# 10_USB_HOST.net
KiCad netlist of a schematic drawn in Altium Designer
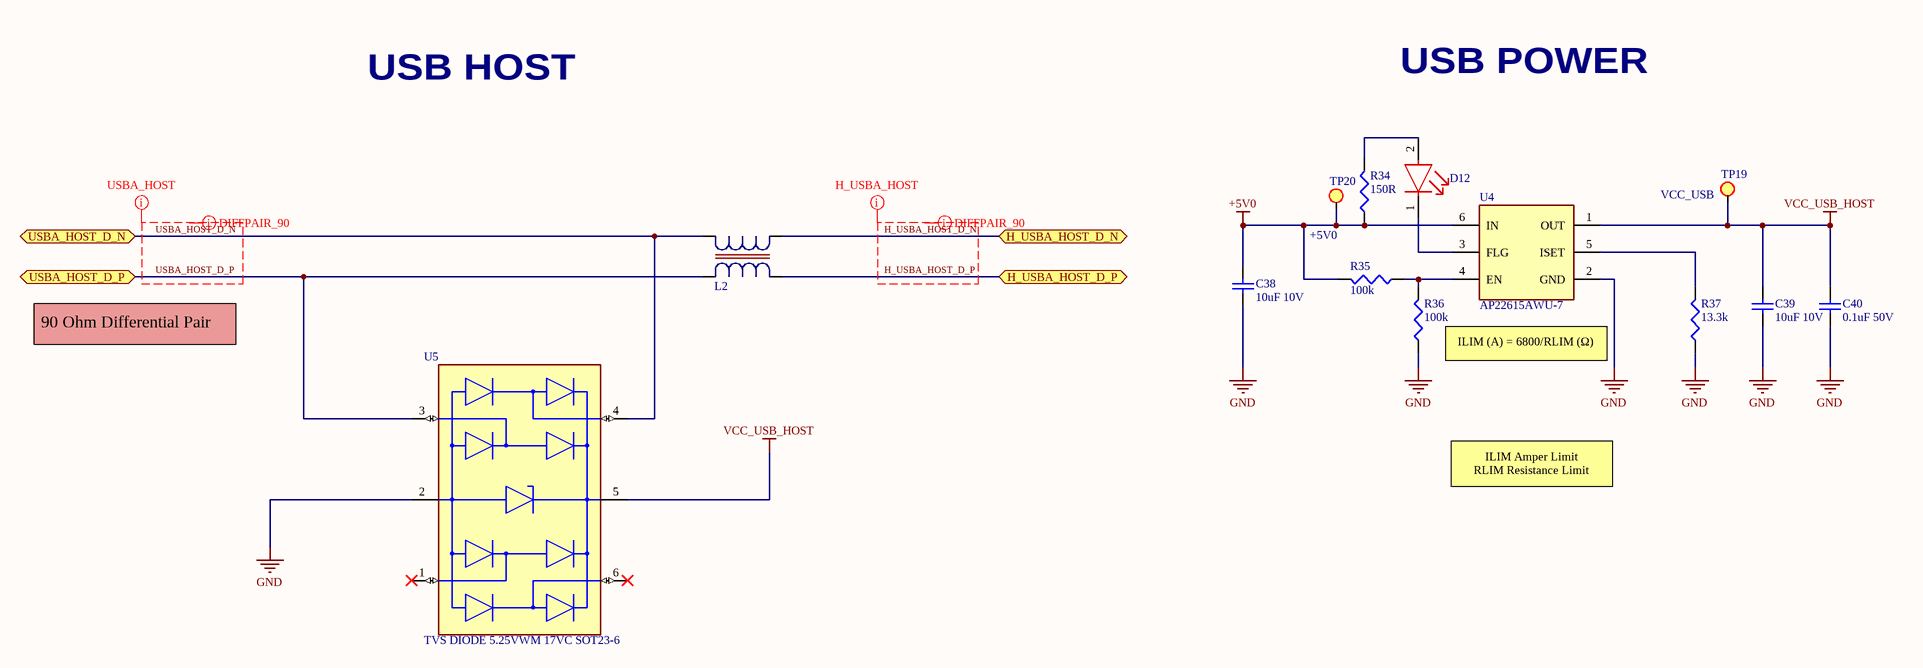
[diagram p0: 10_USB_HOST.SchDoc]

(export (version "E")
  (design (tool "Eeschema 10.0.6"))
  (components
    (comp (ref "C38")
      (value "10uF 10V")
      (footprint "SMC0603")
      (description "10 µF ±10% 10V Ceramic Capacitor X5R 0603 (1608 Metric)")
      (fields
        (field (name "MANUFACTURER PART NUMBER") "CL10A106KP8NNNC")
        (field (name "LCSC PART NUMBER") "C19702")
      )
      (libsource (lib "HW_HOLLAND_NCDM_MONITOR_R1") (part "CAP0603_10UF_10V"))
    )
    (comp (ref "C39")
      (value "10uF 10V")
      (footprint "SMC0603")
      (description "10 µF ±10% 10V Ceramic Capacitor X5R 0603 (1608 Metric)")
      (fields
        (field (name "MANUFACTURER PART NUMBER") "CL10A106KP8NNNC")
        (field (name "LCSC PART NUMBER") "C19702")
      )
      (libsource (lib "HW_HOLLAND_NCDM_MONITOR_R1") (part "CAP0603_10UF_10V"))
    )
    (comp (ref "C40")
      (value "0.1uF 50V")
      (footprint "CAP0402(1005)x0.5")
      (description "0.1 µF ±10% 50V Ceramic Capacitor X7R 0402 (1005 Metric)")
      (fields
        (field (name "MANUFACTURER PART NUMBER") "CL05B104KB54PNC")
        (field (name "LCSC PART NUMBER") "C307331")
      )
      (libsource (lib "HW_HOLLAND_NCDM_MONITOR_R1") (part "CAP0402_0.1UF_50V"))
    )
    (comp (ref "D12")
      (value "LED RED CLEAR SMD")
      (footprint "Lite-On_0_MFG")
      (description "Red 631nm LED Indication - Discrete 2V 0603 (1608 Metric)")
      (fields
        (field (name "MANUFACTURER PART NUMBER") "LTST-C191KRKT")
        (field (name "LCSC PART NUMBER") "C125099")
      )
      (libsource (lib "HW_HOLLAND_NCDM_MONITOR_R1") (part "LTST-C191KRKT"))
    )
    (comp (ref "L2")
      (value "CMC 100MA 2LN 90 OHM SMD")
      (footprint "IND_MCZ1210AH_TDK")
      (description "2 Line Common Mode Choke Surface Mount 90 Ohms @ 100 MHz 100mA DCR 1.75Ohm")
      (fields
        (field (name "MANUFACTURER PART NUMBER") "MCZ1210AH900L2TA0G")
        (field (name "LCSC MANUFACTURER PART NUMBER") "MCZ1210AH900L2TD0G")
      )
      (libsource (lib "HW_HOLLAND_NCDM_MONITOR_R1") (part "MCZ1210AH900L2T"))
    )
    (comp (ref "R34")
      (value "150R")
      (footprint "SMR0603")
      (description "150 Ohms ±1% 0.1W, 1/10W Chip Resistor 0603 (1608 Metric) Moisture Resistant Thick Film")
      (fields
        (field (name "MANUFACTURER PART NUMBER") "RC0603FR-07150RL")
        (field (name "LCSC PART NUMBER") "C114608")
      )
      (libsource (lib "HW_HOLLAND_NCDM_MONITOR_R1") (part "RES0603_150R_%1"))
    )
    (comp (ref "R35")
      (value "100k")
      (footprint "RES0402(1005)")
      (description "100 kOhms ±1% 0.063W, 1/16W Chip Resistor 0402 (1005 Metric) Moisture Resistant Thick Film")
      (fields
        (field (name "MANUFACTURER PART NUMBER") "RC0402FR-07100KL")
        (field (name "LCSC PART NUMBER") "C60491")
      )
      (libsource (lib "HW_HOLLAND_NCDM_MONITOR_R1") (part "RES0402_100K_%1"))
    )
    (comp (ref "R36")
      (value "100k")
      (footprint "RES0402(1005)")
      (description "100 kOhms ±1% 0.063W, 1/16W Chip Resistor 0402 (1005 Metric) Moisture Resistant Thick Film")
      (fields
        (field (name "MANUFACTURER PART NUMBER") "RC0402FR-07100KL")
        (field (name "LCSC PART NUMBER") "C60491")
      )
      (libsource (lib "HW_HOLLAND_NCDM_MONITOR_R1") (part "RES0402_100K_%1"))
    )
    (comp (ref "R37")
      (value "13.3k")
      (footprint "RES0402(1005)")
      (description "RES 13.3K OHM 1% 1/16W 0402")
      (fields
        (field (name "MANUFACTURER PART NUMBER") "RC0402FR-0713K3L")
        (field (name "LCSC PART NUMBER") "C274352")
      )
      (libsource (lib "HW_HOLLAND_NCDM_MONITOR_R1") (part "RES0402_13K3_%1"))
    )
    (comp (ref "TP19")
      (value "VCC_USB")
      (footprint "TEST_POINT")
      (libsource (lib "HW_HOLLAND_NCDM_MONITOR_R1") (part "TP_1"))
    )
    (comp (ref "TP20")
      (value "+5V0")
      (footprint "TEST_POINT")
      (libsource (lib "HW_HOLLAND_NCDM_MONITOR_R1") (part "TP_1"))
    )
    (comp (ref "U4")
      (value "IC PWR SWTCH N/P-CHAN 1:1 TSOT26")
      (footprint "SOT95P280X100-6N")
      (description "Power Switch/Driver 1:1 N/P-Channel 3A TSOT-26")
      (fields
        (field (name "LCSC MANUFACTURER PART NUMBER") "AP22615AWU-7")
        (field (name "LCSC PART NUMBER") "C2680357")
        (field (name "MANUFACTURER PART NUMBER") "AP22615AWU-7")
      )
      (libsource (lib "HW_HOLLAND_NCDM_MONITOR_R1") (part "AP22615AWU-7"))
    )
    (comp (ref "U5")
      (value "TVS DIODE 5.25VWM 17VC SOT23-6")
      (footprint "SOT95P280X145-6N")
      (description "17V Clamp 5A (8/20µs) Ipp Tvs Diode Surface Mount SOT-23-6")
      (fields
        (field (name "MANUFACTURER PART NUMBER") "USBLC6-4SC6")
        (field (name "LCSC PART NUMBER") "C111212")
      )
      (libsource (lib "HW_HOLLAND_NCDM_MONITOR_R1") (part "USBLC6-4SC6"))
    )
  )
  (nets
    (net (code "1") (name "+5V0") (class "Default")
      (node (ref "C38") (pin "2") (pinfunction "2_2") (pintype "passive"))
      (node (ref "R34") (pin "1") (pinfunction "1_1") (pintype "passive"))
      (node (ref "R35") (pin "2") (pinfunction "2_2") (pintype "passive"))
      (node (ref "TP20") (pin "1") (pinfunction "TP_1") (pintype "passive"))
      (node (ref "U4") (pin "6") (pinfunction "IN_6") (pintype "passive"))
    )
    (net (code "2") (name "/H_USBA_HOST_D_N") (class "Default")
      (node (ref "L2") (pin "3") (pinfunction "4_3") (pintype "passive"))
    )
    (net (code "3") (name "/H_USBA_HOST_D_P") (class "Default")
      (node (ref "L2") (pin "4") (pinfunction "4_4") (pintype "passive"))
    )
    (net (code "4") (name "/USBA_HOST_D_N") (class "Default")
      (node (ref "L2") (pin "2") (pinfunction "2_2") (pintype "passive"))
      (node (ref "U5") (pin "4") (pinfunction "I/O3_4") (pintype "bidirectional"))
    )
    (net (code "5") (name "/USBA_HOST_D_P") (class "Default")
      (node (ref "L2") (pin "1") (pinfunction "1_1") (pintype "passive"))
      (node (ref "U5") (pin "3") (pinfunction "I/O2_3") (pintype "bidirectional"))
    )
    (net (code "6") (name "GND") (class "Default")
      (node (ref "C38") (pin "1") (pinfunction "1_1") (pintype "passive"))
      (node (ref "C39") (pin "1") (pinfunction "1_1") (pintype "passive"))
      (node (ref "C40") (pin "1") (pinfunction "1_1") (pintype "passive"))
      (node (ref "R36") (pin "1") (pinfunction "1_1") (pintype "passive"))
      (node (ref "R37") (pin "1") (pinfunction "1_1") (pintype "passive"))
      (node (ref "U4") (pin "2") (pinfunction "GND_2") (pintype "passive"))
      (node (ref "U5") (pin "2") (pinfunction "GND_2") (pintype "passive"))
    )
    (net (code "7") (name "Net-(D12-A)") (class "Default")
      (node (ref "D12") (pin "2") (pinfunction "A_2") (pintype "passive"))
      (node (ref "R34") (pin "2") (pinfunction "2_2") (pintype "passive"))
    )
    (net (code "8") (name "Net-(D12-C)") (class "Default")
      (node (ref "D12") (pin "1") (pinfunction "C_1") (pintype "passive"))
      (node (ref "U4") (pin "3") (pinfunction "FLG_3") (pintype "passive"))
    )
    (net (code "9") (name "Net-(U4-EN)") (class "Default")
      (node (ref "R35") (pin "1") (pinfunction "1_1") (pintype "passive"))
      (node (ref "R36") (pin "2") (pinfunction "2_2") (pintype "passive"))
      (node (ref "U4") (pin "4") (pinfunction "EN_4") (pintype "passive"))
    )
    (net (code "10") (name "Net-(U4-ISET)") (class "Default")
      (node (ref "R37") (pin "2") (pinfunction "2_2") (pintype "passive"))
      (node (ref "U4") (pin "5") (pinfunction "ISET_5") (pintype "passive"))
    )
    (net (code "11") (name "VCC_USB_HOST") (class "Default")
      (node (ref "C39") (pin "2") (pinfunction "2_2") (pintype "passive"))
      (node (ref "C40") (pin "2") (pinfunction "2_2") (pintype "passive"))
      (node (ref "TP19") (pin "1") (pinfunction "TP_1") (pintype "passive"))
      (node (ref "U4") (pin "1") (pinfunction "OUT_1") (pintype "passive"))
      (node (ref "U5") (pin "5") (pinfunction "VP_5") (pintype "power_in"))
    )
    (net (code "12") (name "unconnected-(U5-I{slash}O1-Pad1)") (class "Default")
      (node (ref "U5") (pin "1") (pinfunction "I/O1_1") (pintype "bidirectional+no_connect"))
    )
    (net (code "13") (name "unconnected-(U5-I{slash}O4-Pad6)") (class "Default")
      (node (ref "U5") (pin "6") (pinfunction "I/O4_6") (pintype "bidirectional+no_connect"))
    )
  )
)
